# Sheet1.net
KiCad netlist of a schematic drawn in Altium Designer
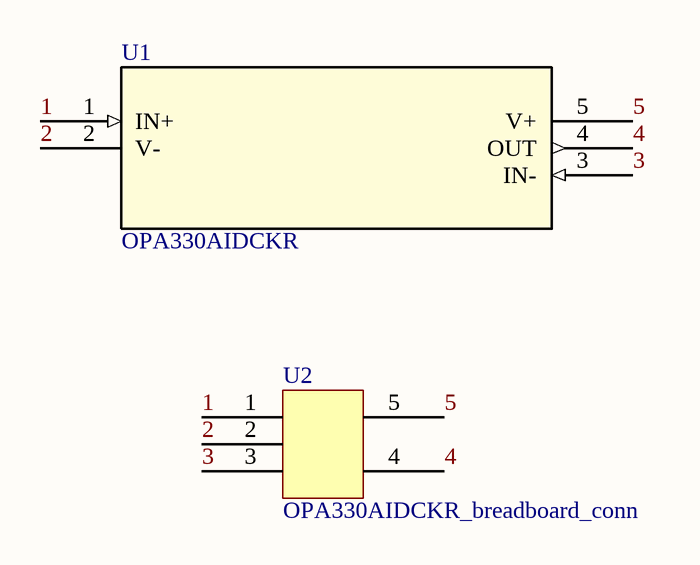
[diagram p0: Sheet1.SchDoc]

(export (version "E")
  (design (tool "Eeschema 10.0.6"))
  (components
    (comp (ref "U1")
      (value "OPA330AIDCKR")
      (footprint "DCK5")
      (description "No Description Available")
      (libsource (lib "OPA330AIDCKR") (part "OPA330AIDCKR"))
    )
    (comp (ref "U2")
      (value "OPA330AIDCKR_breadboard_conn")
      (footprint "OPA330AIDCKR_breadboard_conn")
      (libsource (lib "Schlib1") (part "OPA330AIDCKR_breadboard_conn"))
    )
  )
  (nets
    (net (code "1") (name "/1") (class "Default")
      (node (ref "U1") (pin "1") (pinfunction "IN+_1") (pintype "input"))
      (node (ref "U2") (pin "1") (pintype "passive"))
    )
    (net (code "2") (name "/2") (class "Default")
      (node (ref "U1") (pin "2") (pinfunction "V-_2") (pintype "power_in"))
      (node (ref "U2") (pin "2") (pintype "passive"))
    )
    (net (code "3") (name "/3") (class "Default")
      (node (ref "U1") (pin "3") (pinfunction "IN-_3") (pintype "input"))
      (node (ref "U2") (pin "3") (pintype "passive"))
    )
    (net (code "4") (name "/4") (class "Default")
      (node (ref "U1") (pin "4") (pinfunction "OUT_4") (pintype "output"))
      (node (ref "U2") (pin "4") (pintype "passive"))
    )
    (net (code "5") (name "/5") (class "Default")
      (node (ref "U1") (pin "5") (pinfunction "V+_5") (pintype "power_in"))
      (node (ref "U2") (pin "5") (pintype "passive"))
    )
  )
)
